# LM324LevelSensor.net
KiCad netlist of a schematic drawn in EAGLE
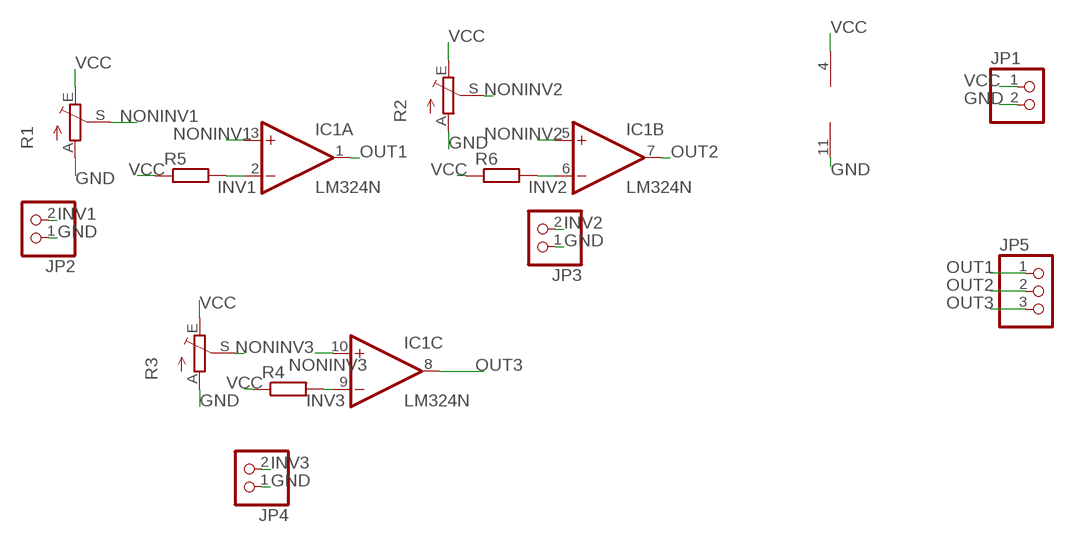
[diagram p0: schematic, sheet 1]

(export (version "E")
  (design (tool "Eeschema 10.0.6"))
  (components
    (comp (ref "IC1")
      (value "LM324N")
      (footprint "eagle-import:DIL14")
      (libsource (lib "eagle-import") (part "LM324N"))
    )
    (comp (ref "JP1")
      (value "PINHD-1X2")
      (footprint "eagle-import:1X02")
      (libsource (lib "eagle-import") (part "PINHD-1X2"))
    )
    (comp (ref "JP2")
      (value "PINHD-1X2")
      (footprint "eagle-import:1X02")
      (libsource (lib "eagle-import") (part "PINHD-1X2"))
    )
    (comp (ref "JP3")
      (value "PINHD-1X2")
      (footprint "eagle-import:1X02")
      (libsource (lib "eagle-import") (part "PINHD-1X2"))
    )
    (comp (ref "JP4")
      (value "PINHD-1X2")
      (footprint "eagle-import:1X02")
      (libsource (lib "eagle-import") (part "PINHD-1X2"))
    )
    (comp (ref "JP5")
      (value "PINHD-1X3")
      (footprint "eagle-import:1X03")
      (libsource (lib "eagle-import") (part "PINHD-1X3"))
    )
    (comp (ref "R1")
      (value "TRIM_EU-B25P")
      (footprint "eagle-import:B25P")
      (libsource (lib "eagle-import") (part "TRIM_EU-B25P"))
    )
    (comp (ref "R2")
      (value "TRIM_EU-B25P")
      (footprint "eagle-import:B25P")
      (libsource (lib "eagle-import") (part "TRIM_EU-B25P"))
    )
    (comp (ref "R3")
      (value "TRIM_EU-B25P")
      (footprint "eagle-import:B25P")
      (libsource (lib "eagle-import") (part "TRIM_EU-B25P"))
    )
    (comp (ref "R4")
      (value "R-EU_0204/7")
      (footprint "eagle-import:0204_7")
      (libsource (lib "eagle-import") (part "R-EU_0204/7"))
    )
    (comp (ref "R5")
      (value "R-EU_0204/7")
      (footprint "eagle-import:0204_7")
      (libsource (lib "eagle-import") (part "R-EU_0204/7"))
    )
    (comp (ref "R6")
      (value "R-EU_0204/7")
      (footprint "eagle-import:0204_7")
      (libsource (lib "eagle-import") (part "R-EU_0204/7"))
    )
  )
  (nets
    (net (code "1") (name "/GND") (class "Default")
      (node (ref "IC1") (pin "11") (pinfunction "V-_11") (pintype "power_in"))
      (node (ref "JP1") (pin "2") (pinfunction "2_2") (pintype "passive"))
      (node (ref "JP2") (pin "1") (pinfunction "1_1") (pintype "passive"))
      (node (ref "JP3") (pin "1") (pinfunction "1_1") (pintype "passive"))
      (node (ref "JP4") (pin "1") (pinfunction "1_1") (pintype "passive"))
      (node (ref "R1") (pin "A") (pinfunction "A_A") (pintype "passive"))
      (node (ref "R2") (pin "A") (pinfunction "A_A") (pintype "passive"))
      (node (ref "R3") (pin "A") (pinfunction "A_A") (pintype "passive"))
    )
    (net (code "2") (name "/INV1") (class "Default")
      (node (ref "IC1") (pin "2") (pinfunction "-IN_2") (pintype "input"))
      (node (ref "JP2") (pin "2") (pinfunction "2_2") (pintype "passive"))
      (node (ref "R5") (pin "2") (pinfunction "2_2") (pintype "passive"))
    )
    (net (code "3") (name "/INV2") (class "Default")
      (node (ref "IC1") (pin "6") (pinfunction "-IN_6") (pintype "input"))
      (node (ref "JP3") (pin "2") (pinfunction "2_2") (pintype "passive"))
      (node (ref "R6") (pin "2") (pinfunction "2_2") (pintype "passive"))
    )
    (net (code "4") (name "/INV3") (class "Default")
      (node (ref "IC1") (pin "9") (pinfunction "-IN_9") (pintype "input"))
      (node (ref "JP4") (pin "2") (pinfunction "2_2") (pintype "passive"))
      (node (ref "R4") (pin "2") (pinfunction "2_2") (pintype "passive"))
    )
    (net (code "5") (name "/NONINV1") (class "Default")
      (node (ref "IC1") (pin "3") (pinfunction "+IN_3") (pintype "input"))
      (node (ref "R1") (pin "S") (pinfunction "S_S") (pintype "passive"))
    )
    (net (code "6") (name "/NONINV2") (class "Default")
      (node (ref "IC1") (pin "5") (pinfunction "+IN_5") (pintype "input"))
      (node (ref "R2") (pin "S") (pinfunction "S_S") (pintype "passive"))
    )
    (net (code "7") (name "/NONINV3") (class "Default")
      (node (ref "IC1") (pin "10") (pinfunction "+IN_10") (pintype "input"))
      (node (ref "R3") (pin "S") (pinfunction "S_S") (pintype "passive"))
    )
    (net (code "8") (name "/OUT1") (class "Default")
      (node (ref "IC1") (pin "1") (pinfunction "OUT_1") (pintype "output"))
      (node (ref "JP5") (pin "1") (pinfunction "1_1") (pintype "passive"))
    )
    (net (code "9") (name "/OUT2") (class "Default")
      (node (ref "IC1") (pin "7") (pinfunction "OUT_7") (pintype "output"))
      (node (ref "JP5") (pin "2") (pinfunction "2_2") (pintype "passive"))
    )
    (net (code "10") (name "/OUT3") (class "Default")
      (node (ref "IC1") (pin "8") (pinfunction "OUT_8") (pintype "output"))
      (node (ref "JP5") (pin "3") (pinfunction "3_3") (pintype "passive"))
    )
    (net (code "11") (name "/VCC") (class "Default")
      (node (ref "IC1") (pin "4") (pinfunction "V+_4") (pintype "power_in"))
      (node (ref "JP1") (pin "1") (pinfunction "1_1") (pintype "passive"))
      (node (ref "R1") (pin "E") (pinfunction "E_E") (pintype "passive"))
      (node (ref "R2") (pin "E") (pinfunction "E_E") (pintype "passive"))
      (node (ref "R3") (pin "E") (pinfunction "E_E") (pintype "passive"))
      (node (ref "R4") (pin "1") (pinfunction "1_1") (pintype "passive"))
      (node (ref "R5") (pin "1") (pinfunction "1_1") (pintype "passive"))
      (node (ref "R6") (pin "1") (pinfunction "1_1") (pintype "passive"))
    )
  )
)
